# nguyen_l.net
KiCad netlist of a schematic drawn in Altium Designer
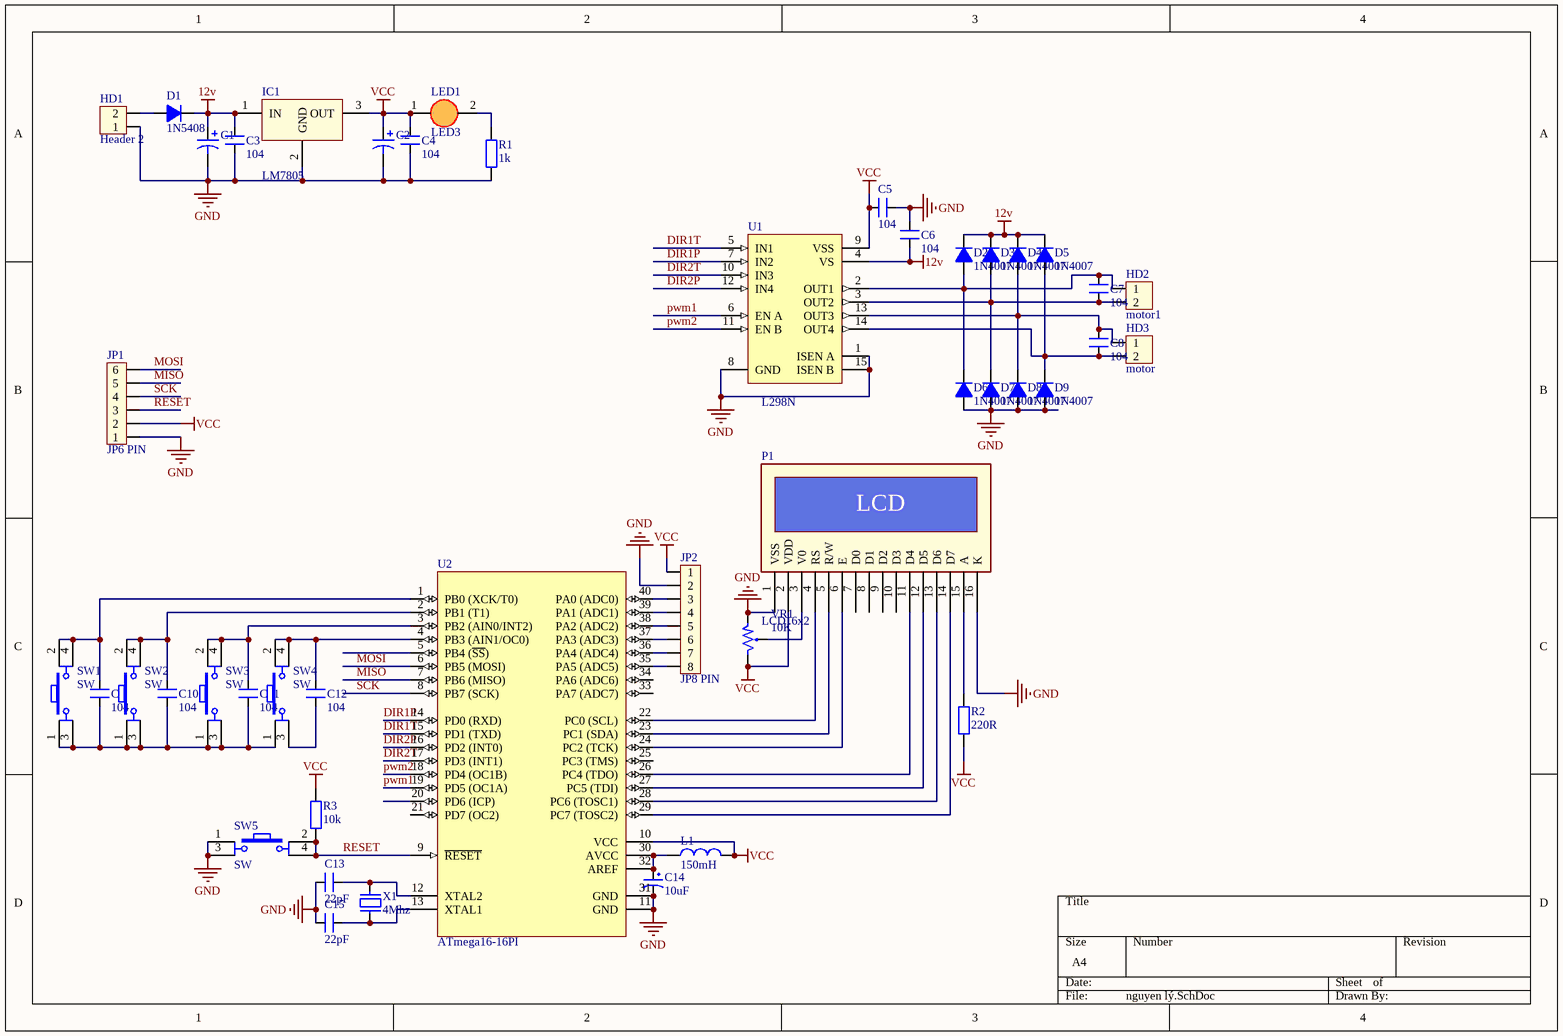
[diagram p0: nguyen lý.SchDoc]

(export (version "E")
  (design (tool "Eeschema 10.0.6"))
  (components
    (comp (ref "C1")
      (value "Cap Pol 8mm")
      (footprint "C10mm")
      (description "Polarized Capacitor (Axial)")
      (fields (field (name "PUBLISHER") "Altium Limited"))
      (libsource (lib "thu vien") (part "Cap Pol 8mm"))
    )
    (comp (ref "C2")
      (value "Cap Pol 8mm")
      (footprint "C10mm")
      (description "Polarized Capacitor (Axial)")
      (fields (field (name "PUBLISHER") "Altium Limited"))
      (libsource (lib "thu vien") (part "Cap Pol 8mm"))
    )
    (comp (ref "C3")
      (value "104")
      (footprint "CN2")
      (description "Cap np Cremic Value  104pF => 105pF")
      (libsource (lib "syhaunguyen") (part "CN2"))
    )
    (comp (ref "C4")
      (value "104")
      (footprint "CN2")
      (description "Cap np Cremic Value  104pF => 105pF")
      (libsource (lib "syhaunguyen") (part "CN2"))
    )
    (comp (ref "C5")
      (value "104")
      (footprint "CN2")
      (description "Cap np Cremic Value  104pF => 105pF")
      (libsource (lib "syhaunguyen") (part "CN2"))
    )
    (comp (ref "C6")
      (value "104")
      (footprint "CN2")
      (description "Cap np Cremic Value  104pF => 105pF")
      (libsource (lib "syhaunguyen") (part "CN2"))
    )
    (comp (ref "C7")
      (value "104")
      (footprint "CN2")
      (description "Cap np Cremic Value  104pF => 105pF")
      (libsource (lib "syhaunguyen") (part "CN2"))
    )
    (comp (ref "C8")
      (value "104")
      (footprint "CN2")
      (description "Cap np Cremic Value  104pF => 105pF")
      (libsource (lib "syhaunguyen") (part "CN2"))
    )
    (comp (ref "C9")
      (value "104")
      (footprint "CN1.5")
      (description "Cap np Cremic  682pF => 104 pF")
      (libsource (lib "syhaunguyen") (part "CN1.5"))
    )
    (comp (ref "C10")
      (value "104")
      (footprint "CN1.5")
      (description "Cap np Cremic  682pF => 104 pF")
      (libsource (lib "syhaunguyen") (part "CN1.5"))
    )
    (comp (ref "C11")
      (value "104")
      (footprint "CN1.5")
      (description "Cap np Cremic  682pF => 104 pF")
      (libsource (lib "syhaunguyen") (part "CN1.5"))
    )
    (comp (ref "C12")
      (value "104")
      (footprint "CN1.5")
      (description "Cap np Cremic  682pF => 104 pF")
      (libsource (lib "syhaunguyen") (part "CN1.5"))
    )
    (comp (ref "C13")
      (value "22pF")
      (footprint "CN1")
      (description "Cap np Cremic Value  1pF => 472 pF")
      (libsource (lib "syhaunguyen") (part "CN1"))
    )
    (comp (ref "C14")
      (value "10uF")
      (footprint "CP1/2")
      (description "Cap P  0,1uF < 22uF , 16 - 50V")
      (libsource (lib "syhaunguyen") (part "CP1"))
    )
    (comp (ref "C15")
      (value "22pF")
      (footprint "CN1")
      (description "Cap np Cremic Value  1pF => 472 pF")
      (libsource (lib "syhaunguyen") (part "CN1"))
    )
    (comp (ref "D1")
      (value "1N5408")
      (footprint "D5A")
      (description "Diode 5A")
      (libsource (lib "syhaunguyen") (part "D5A"))
    )
    (comp (ref "D2")
      (value "1N4007")
      (footprint "D1A")
      (description "Diode 1A")
      (libsource (lib "syhaunguyen") (part "D1A"))
    )
    (comp (ref "D3")
      (value "1N4007")
      (footprint "D1A")
      (description "Diode 1A")
      (libsource (lib "syhaunguyen") (part "D1A"))
    )
    (comp (ref "D4")
      (value "1N4007")
      (footprint "D1A")
      (description "Diode 1A")
      (libsource (lib "syhaunguyen") (part "D1A"))
    )
    (comp (ref "D5")
      (value "1N4007")
      (footprint "D1A")
      (description "Diode 1A")
      (libsource (lib "syhaunguyen") (part "D1A"))
    )
    (comp (ref "D6")
      (value "1N4007")
      (footprint "D1A")
      (description "Diode 1A")
      (libsource (lib "syhaunguyen") (part "D1A"))
    )
    (comp (ref "D7")
      (value "1N4007")
      (footprint "D1A")
      (description "Diode 1A")
      (libsource (lib "syhaunguyen") (part "D1A"))
    )
    (comp (ref "D8")
      (value "1N4007")
      (footprint "D1A")
      (description "Diode 1A")
      (libsource (lib "syhaunguyen") (part "D1A"))
    )
    (comp (ref "D9")
      (value "1N4007")
      (footprint "D1A")
      (description "Diode 1A")
      (libsource (lib "syhaunguyen") (part "D1A"))
    )
    (comp (ref "HD1")
      (value "Header 2")
      (footprint "HED2")
      (description "Header 2 (Green)")
      (libsource (lib "") (part "Hed2_1"))
    )
    (comp (ref "HD2")
      (value "motor1")
      (footprint "HED2")
      (description "Header 2 (Green)")
      (libsource (lib "syhaunguyen") (part "Hed2"))
    )
    (comp (ref "HD3")
      (value "motor")
      (footprint "HED2")
      (description "Header 2 (Green)")
      (libsource (lib "syhaunguyen") (part "Hed2"))
    )
    (comp (ref "IC1")
      (value "LM7805")
      (footprint "TO-220")
      (description "On ap +, from + 5 to + 24VDC")
      (libsource (lib "syhaunguyen") (part "LM78xx"))
    )
    (comp (ref "JP1") (value "JP6 PIN") (footprint "JP6") (libsource (lib "syhaunguyen") (part "JP6")))
    (comp (ref "JP2") (value "JP8 PIN") (footprint "JP8") (libsource (lib "syhaunguyen") (part "JP8")))
    (comp (ref "L1")
      (value "150mH")
      (footprint "L/0.4")
      (description "Inductor")
      (libsource (lib "syhaunguyen") (part "L1"))
    )
    (comp (ref "LED1")
      (value "LED3")
      (footprint "LED3mm")
      (description "LED 3mm")
      (libsource (lib "thu vien") (part "LED 3mm"))
    )
    (comp (ref "P1") (value "LCD16x2") (footprint "LCD16X2N") (libsource (lib "thu vien") (part "LCD Text")))
    (comp (ref "R1")
      (value "1k")
      (footprint "R1/4W")
      (description "Resistor 1/4W")
      (libsource (lib "syhaunguyen") (part "R1/4W"))
    )
    (comp (ref "R2")
      (value "220R")
      (footprint "R1/4W")
      (description "Resistor 1/4W")
      (libsource (lib "syhaunguyen") (part "R1/4W"))
    )
    (comp (ref "R3")
      (value "10k")
      (footprint "R1/4W")
      (description "Resistor 1/4W")
      (libsource (lib "syhaunguyen") (part "R1/4W"))
    )
    (comp (ref "SW1")
      (value "SW")
      (footprint "SW4")
      (description "Switch button 4 pin")
      (libsource (lib "syhaunguyen") (part "SW4"))
    )
    (comp (ref "SW2")
      (value "SW")
      (footprint "SW4")
      (description "Switch button 4 pin")
      (libsource (lib "syhaunguyen") (part "SW4"))
    )
    (comp (ref "SW3")
      (value "SW")
      (footprint "SW4")
      (description "Switch button 4 pin")
      (libsource (lib "syhaunguyen") (part "SW4"))
    )
    (comp (ref "SW4")
      (value "SW")
      (footprint "SW4")
      (description "Switch button 4 pin")
      (libsource (lib "syhaunguyen") (part "SW4"))
    )
    (comp (ref "SW5")
      (value "SW")
      (footprint "SW4")
      (description "Switch button 4 pin")
      (libsource (lib "") (part "SW4_1"))
    )
    (comp (ref "U1")
      (value "L298N")
      (footprint "DIP15SL2")
      (description "Dual Full Bridge Driver")
      (fields (field (name "PUBLISHER") "Altium Limited"))
      (libsource (lib "thu vien") (part "L298N"))
    )
    (comp (ref "U2")
      (value "ATmega16-16PI")
      (footprint "DIP40/W0.6")
      (description "8-Bit AVR Microcontroller with 16K Bytes of In-System Programmable Flash Memory")
      (fields (field (name "PUBLISHER") "Altium Limited"))
      (libsource (lib "thu vien") (part "ATmega16-16PI"))
    )
    (comp (ref "VR1")
      (value "10K")
      (footprint "VR1")
      (description "Var Resistor")
      (libsource (lib "syhaunguyen") (part "VR1"))
    )
    (comp (ref "X1")
      (value "4Mhz")
      (footprint "XT2")
      (description "Crystal For all Crystal 2pin.")
      (libsource (lib "syhaunguyen") (part "XT2"))
    )
  )
  (nets
    (net (code "1") (name "/DIR1P") (class "Default")
      (node (ref "U1") (pin "7") (pinfunction "IN2_7") (pintype "input"))
      (node (ref "U2") (pin "14") (pinfunction "PD0_(RXD)_14") (pintype "bidirectional"))
    )
    (net (code "2") (name "/DIR1T") (class "Default")
      (node (ref "U1") (pin "5") (pinfunction "IN1_5") (pintype "input"))
      (node (ref "U2") (pin "15") (pinfunction "PD1_(TXD)_15") (pintype "bidirectional"))
    )
    (net (code "3") (name "/DIR2P") (class "Default")
      (node (ref "U1") (pin "12") (pinfunction "IN4_12") (pintype "input"))
      (node (ref "U2") (pin "16") (pinfunction "PD2_(INT0)_16") (pintype "bidirectional"))
    )
    (net (code "4") (name "/DIR2T") (class "Default")
      (node (ref "U1") (pin "10") (pinfunction "IN3_10") (pintype "input"))
      (node (ref "U2") (pin "17") (pinfunction "PD3_(INT1)_17") (pintype "bidirectional"))
    )
    (net (code "5") (name "/MISO") (class "Default")
      (node (ref "JP1") (pin "5") (pinfunction "5_5") (pintype "passive"))
      (node (ref "U2") (pin "7") (pinfunction "PB6_(MISO)_7") (pintype "bidirectional"))
    )
    (net (code "6") (name "/MOSI") (class "Default")
      (node (ref "JP1") (pin "6") (pinfunction "6_6") (pintype "passive"))
      (node (ref "U2") (pin "6") (pinfunction "PB5_(MOSI)_6") (pintype "bidirectional"))
    )
    (net (code "7") (name "/RESET") (class "Default")
      (node (ref "JP1") (pin "3") (pinfunction "3_3") (pintype "passive"))
      (node (ref "R3") (pin "1") (pinfunction "1_1") (pintype "passive"))
      (node (ref "SW5") (pin "2") (pintype "passive"))
      (node (ref "SW5") (pin "4") (pintype "passive"))
      (node (ref "U2") (pin "9") (pinfunction "~{RESET}_9") (pintype "input"))
    )
    (net (code "8") (name "/SCK") (class "Default")
      (node (ref "JP1") (pin "4") (pinfunction "4_4") (pintype "passive"))
      (node (ref "U2") (pin "8") (pinfunction "PB7_(SCK)_8") (pintype "bidirectional"))
    )
    (net (code "9") (name "/pwm1") (class "Default")
      (node (ref "U1") (pin "6") (pinfunction "EN_A_6") (pintype "input"))
      (node (ref "U2") (pin "19") (pinfunction "PD5_(OC1A)_19") (pintype "bidirectional"))
    )
    (net (code "10") (name "/pwm2") (class "Default")
      (node (ref "U1") (pin "11") (pinfunction "EN_B_11") (pintype "input"))
      (node (ref "U2") (pin "18") (pinfunction "PD4_(OC1B)_18") (pintype "bidirectional"))
    )
    (net (code "11") (name "12v") (class "Default")
      (node (ref "C1") (pin "1") (pinfunction "1_1") (pintype "passive"))
      (node (ref "C3") (pin "2") (pinfunction "2_2") (pintype "passive"))
      (node (ref "C6") (pin "1") (pinfunction "1_1") (pintype "passive"))
      (node (ref "D1") (pin "2") (pinfunction "K_2") (pintype "passive"))
      (node (ref "D2") (pin "2") (pinfunction "K_2") (pintype "passive"))
      (node (ref "D3") (pin "2") (pinfunction "K_2") (pintype "passive"))
      (node (ref "D4") (pin "2") (pinfunction "K_2") (pintype "passive"))
      (node (ref "D5") (pin "2") (pinfunction "K_2") (pintype "passive"))
      (node (ref "IC1") (pin "1") (pinfunction "IN_1") (pintype "passive"))
      (node (ref "U1") (pin "4") (pinfunction "VS_4") (pintype "power_in"))
    )
    (net (code "12") (name "GND") (class "Default")
      (node (ref "C1") (pin "2") (pinfunction "2_2") (pintype "passive"))
      (node (ref "C13") (pin "1") (pinfunction "1_1") (pintype "passive"))
      (node (ref "C14") (pin "2") (pinfunction "2_2") (pintype "passive"))
      (node (ref "C15") (pin "1") (pinfunction "1_1") (pintype "passive"))
      (node (ref "C2") (pin "2") (pinfunction "2_2") (pintype "passive"))
      (node (ref "C3") (pin "1") (pinfunction "1_1") (pintype "passive"))
      (node (ref "C4") (pin "1") (pinfunction "1_1") (pintype "passive"))
      (node (ref "C5") (pin "2") (pinfunction "2_2") (pintype "passive"))
      (node (ref "C6") (pin "2") (pinfunction "2_2") (pintype "passive"))
      (node (ref "D6") (pin "1") (pinfunction "A_1") (pintype "passive"))
      (node (ref "D7") (pin "1") (pinfunction "A_1") (pintype "passive"))
      (node (ref "D8") (pin "1") (pinfunction "A_1") (pintype "passive"))
      (node (ref "D9") (pin "1") (pinfunction "A_1") (pintype "passive"))
      (node (ref "HD1") (pin "1") (pinfunction "1_1") (pintype "passive"))
      (node (ref "IC1") (pin "2") (pinfunction "GND_2") (pintype "passive"))
      (node (ref "JP1") (pin "1") (pinfunction "1_1") (pintype "passive"))
      (node (ref "JP2") (pin "2") (pinfunction "2_2") (pintype "passive"))
      (node (ref "P1") (pin "1") (pinfunction "VSS_1") (pintype "passive"))
      (node (ref "P1") (pin "16") (pinfunction "K_16") (pintype "passive"))
      (node (ref "R1") (pin "1") (pinfunction "1_1") (pintype "passive"))
      (node (ref "SW5") (pin "1") (pintype "passive"))
      (node (ref "SW5") (pin "3") (pintype "passive"))
      (node (ref "U1") (pin "1") (pinfunction "ISEN_A_1") (pintype "passive"))
      (node (ref "U1") (pin "15") (pinfunction "ISEN_B_15") (pintype "passive"))
      (node (ref "U1") (pin "8") (pinfunction "GND_8") (pintype "power_in"))
      (node (ref "U2") (pin "11") (pinfunction "GND_11") (pintype "power_in"))
      (node (ref "U2") (pin "31") (pinfunction "GND_31") (pintype "power_in"))
      (node (ref "VR1") (pin "1") (pinfunction "1_1") (pintype "passive"))
    )
    (net (code "13") (name "Net-(C10-Pad1)") (class "Default")
      (node (ref "C10") (pin "1") (pinfunction "1_1") (pintype "passive"))
      (node (ref "C11") (pin "1") (pinfunction "1_1") (pintype "passive"))
      (node (ref "C9") (pin "1") (pinfunction "1_1") (pintype "passive"))
      (node (ref "SW1") (pin "1") (pintype "passive"))
      (node (ref "SW1") (pin "3") (pintype "passive"))
      (node (ref "SW2") (pin "1") (pintype "passive"))
      (node (ref "SW2") (pin "3") (pintype "passive"))
      (node (ref "SW3") (pin "1") (pintype "passive"))
      (node (ref "SW3") (pin "3") (pintype "passive"))
      (node (ref "SW4") (pin "1") (pintype "passive"))
    )
    (net (code "14") (name "Net-(C12-Pad1)") (class "Default")
      (node (ref "C12") (pin "1") (pinfunction "1_1") (pintype "passive"))
      (node (ref "SW4") (pin "3") (pintype "passive"))
    )
    (net (code "15") (name "Net-(D1-A)") (class "Default")
      (node (ref "D1") (pin "1") (pinfunction "A_1") (pintype "passive"))
      (node (ref "HD1") (pin "2") (pinfunction "2_2") (pintype "passive"))
    )
    (net (code "16") (name "Net-(D2-A)") (class "Default")
      (node (ref "C7") (pin "2") (pinfunction "2_2") (pintype "passive"))
      (node (ref "D2") (pin "1") (pinfunction "A_1") (pintype "passive"))
      (node (ref "D6") (pin "2") (pinfunction "K_2") (pintype "passive"))
      (node (ref "HD2") (pin "1") (pinfunction "1_1") (pintype "passive"))
      (node (ref "U1") (pin "2") (pinfunction "OUT1_2") (pintype "output"))
    )
    (net (code "17") (name "Net-(D3-A)") (class "Default")
      (node (ref "C7") (pin "1") (pinfunction "1_1") (pintype "passive"))
      (node (ref "D3") (pin "1") (pinfunction "A_1") (pintype "passive"))
      (node (ref "D7") (pin "2") (pinfunction "K_2") (pintype "passive"))
      (node (ref "HD2") (pin "2") (pinfunction "2_2") (pintype "passive"))
      (node (ref "U1") (pin "3") (pinfunction "OUT2_3") (pintype "output"))
    )
    (net (code "18") (name "Net-(D4-A)") (class "Default")
      (node (ref "C8") (pin "2") (pinfunction "2_2") (pintype "passive"))
      (node (ref "D4") (pin "1") (pinfunction "A_1") (pintype "passive"))
      (node (ref "D8") (pin "2") (pinfunction "K_2") (pintype "passive"))
      (node (ref "HD3") (pin "1") (pinfunction "1_1") (pintype "passive"))
      (node (ref "U1") (pin "13") (pinfunction "OUT3_13") (pintype "output"))
    )
    (net (code "19") (name "Net-(D5-A)") (class "Default")
      (node (ref "C8") (pin "1") (pinfunction "1_1") (pintype "passive"))
      (node (ref "D5") (pin "1") (pinfunction "A_1") (pintype "passive"))
      (node (ref "D9") (pin "2") (pinfunction "K_2") (pintype "passive"))
      (node (ref "HD3") (pin "2") (pinfunction "2_2") (pintype "passive"))
      (node (ref "U1") (pin "14") (pinfunction "OUT4_14") (pintype "output"))
    )
    (net (code "20") (name "Net-(LED1-K)") (class "Default")
      (node (ref "LED1") (pin "2") (pinfunction "K_2") (pintype "passive"))
      (node (ref "R1") (pin "2") (pinfunction "2_2") (pintype "passive"))
    )
    (net (code "21") (name "Net-(P1-A)") (class "Default")
      (node (ref "P1") (pin "15") (pinfunction "A_15") (pintype "passive"))
      (node (ref "R2") (pin "2") (pinfunction "2_2") (pintype "passive"))
    )
    (net (code "22") (name "Net-(P1-D4)") (class "Default")
      (node (ref "P1") (pin "11") (pinfunction "D4_11") (pintype "passive"))
      (node (ref "U2") (pin "26") (pinfunction "PC4_(TDO)_26") (pintype "bidirectional"))
    )
    (net (code "23") (name "Net-(P1-D5)") (class "Default")
      (node (ref "P1") (pin "12") (pinfunction "D5_12") (pintype "passive"))
      (node (ref "U2") (pin "27") (pinfunction "PC5_(TDI)_27") (pintype "bidirectional"))
    )
    (net (code "24") (name "Net-(P1-D6)") (class "Default")
      (node (ref "P1") (pin "13") (pinfunction "D6_13") (pintype "passive"))
      (node (ref "U2") (pin "28") (pinfunction "PC6_(TOSC1)_28") (pintype "bidirectional"))
    )
    (net (code "25") (name "Net-(P1-D7)") (class "Default")
      (node (ref "P1") (pin "14") (pinfunction "D7_14") (pintype "passive"))
      (node (ref "U2") (pin "29") (pinfunction "PC7_(TOSC2)_29") (pintype "bidirectional"))
    )
    (net (code "26") (name "Net-(P1-E)") (class "Default")
      (node (ref "P1") (pin "6") (pinfunction "E_6") (pintype "passive"))
      (node (ref "U2") (pin "24") (pinfunction "PC2_(TCK)_24") (pintype "bidirectional"))
    )
    (net (code "27") (name "Net-(P1-RS)") (class "Default")
      (node (ref "P1") (pin "4") (pinfunction "RS_4") (pintype "passive"))
      (node (ref "U2") (pin "22") (pinfunction "PC0_(SCL)_22") (pintype "bidirectional"))
    )
    (net (code "28") (name "Net-(P1-R{slash}W)") (class "Default")
      (node (ref "P1") (pin "5") (pinfunction "R/W_5") (pintype "passive"))
      (node (ref "U2") (pin "23") (pinfunction "PC1_(SDA)_23") (pintype "bidirectional"))
    )
    (net (code "29") (name "Net-(P1-V0)") (class "Default")
      (node (ref "P1") (pin "3") (pinfunction "V0_3") (pintype "passive"))
      (node (ref "VR1") (pin "2") (pinfunction "2_2") (pintype "passive"))
    )
    (net (code "30") (name "Net-(U2-AREF)") (class "Default")
      (node (ref "C14") (pin "1") (pinfunction "1_1") (pintype "passive"))
      (node (ref "L1") (pin "1") (pinfunction "1_1") (pintype "passive"))
      (node (ref "U2") (pin "30") (pinfunction "AVCC_30") (pintype "power_in"))
      (node (ref "U2") (pin "32") (pinfunction "AREF_32") (pintype "passive"))
    )
    (net (code "31") (name "Net-(U2-PA0_(ADC0))") (class "Default")
      (node (ref "JP2") (pin "3") (pinfunction "3_3") (pintype "passive"))
      (node (ref "U2") (pin "40") (pinfunction "PA0_(ADC0)_40") (pintype "bidirectional"))
    )
    (net (code "32") (name "Net-(U2-PA1_(ADC1))") (class "Default")
      (node (ref "JP2") (pin "4") (pinfunction "4_4") (pintype "passive"))
      (node (ref "U2") (pin "39") (pinfunction "PA1_(ADC1)_39") (pintype "bidirectional"))
    )
    (net (code "33") (name "Net-(U2-PA2_(ADC2))") (class "Default")
      (node (ref "JP2") (pin "5") (pinfunction "5_5") (pintype "passive"))
      (node (ref "U2") (pin "38") (pinfunction "PA2_(ADC2)_38") (pintype "bidirectional"))
    )
    (net (code "34") (name "Net-(U2-PA3_(ADC3))") (class "Default")
      (node (ref "JP2") (pin "6") (pinfunction "6_6") (pintype "passive"))
      (node (ref "U2") (pin "37") (pinfunction "PA3_(ADC3)_37") (pintype "bidirectional"))
    )
    (net (code "35") (name "Net-(U2-PA4_(ADC4))") (class "Default")
      (node (ref "JP2") (pin "7") (pinfunction "7_7") (pintype "passive"))
      (node (ref "U2") (pin "36") (pinfunction "PA4_(ADC4)_36") (pintype "bidirectional"))
    )
    (net (code "36") (name "Net-(U2-PA5_(ADC5))") (class "Default")
      (node (ref "JP2") (pin "8") (pinfunction "8_8") (pintype "passive"))
      (node (ref "U2") (pin "35") (pinfunction "PA5_(ADC5)_35") (pintype "bidirectional"))
    )
    (net (code "37") (name "Net-(U2-PB0_(XCK{slash}T0))") (class "Default")
      (node (ref "C9") (pin "2") (pinfunction "2_2") (pintype "passive"))
      (node (ref "SW1") (pin "2") (pintype "passive"))
      (node (ref "SW1") (pin "4") (pintype "passive"))
      (node (ref "U2") (pin "1") (pinfunction "PB0_(XCK/T0)_1") (pintype "bidirectional"))
    )
    (net (code "38") (name "Net-(U2-PB1_(T1))") (class "Default")
      (node (ref "C10") (pin "2") (pinfunction "2_2") (pintype "passive"))
      (node (ref "SW2") (pin "2") (pintype "passive"))
      (node (ref "SW2") (pin "4") (pintype "passive"))
      (node (ref "U2") (pin "2") (pinfunction "PB1_(T1)_2") (pintype "bidirectional"))
    )
    (net (code "39") (name "Net-(U2-PB2_(AIN0{slash}INT2))") (class "Default")
      (node (ref "C11") (pin "2") (pinfunction "2_2") (pintype "passive"))
      (node (ref "SW3") (pin "2") (pintype "passive"))
      (node (ref "SW3") (pin "4") (pintype "passive"))
      (node (ref "U2") (pin "3") (pinfunction "PB2_(AIN0/INT2)_3") (pintype "bidirectional"))
    )
    (net (code "40") (name "Net-(U2-PB3_(AIN1{slash}OC0))") (class "Default")
      (node (ref "C12") (pin "2") (pinfunction "2_2") (pintype "passive"))
      (node (ref "SW4") (pin "2") (pintype "passive"))
      (node (ref "SW4") (pin "4") (pintype "passive"))
      (node (ref "U2") (pin "4") (pinfunction "PB3_(AIN1/OC0)_4") (pintype "bidirectional"))
    )
    (net (code "41") (name "Net-(U2-XTAL1)") (class "Default")
      (node (ref "C15") (pin "2") (pinfunction "2_2") (pintype "passive"))
      (node (ref "U2") (pin "13") (pinfunction "XTAL1_13") (pintype "passive"))
      (node (ref "X1") (pin "1") (pinfunction "1_1") (pintype "passive"))
    )
    (net (code "42") (name "Net-(U2-XTAL2)") (class "Default")
      (node (ref "C13") (pin "2") (pinfunction "2_2") (pintype "passive"))
      (node (ref "U2") (pin "12") (pinfunction "XTAL2_12") (pintype "passive"))
      (node (ref "X1") (pin "2") (pinfunction "2_2") (pintype "passive"))
    )
    (net (code "43") (name "VCC") (class "Default")
      (node (ref "C2") (pin "1") (pinfunction "1_1") (pintype "passive"))
      (node (ref "C4") (pin "2") (pinfunction "2_2") (pintype "passive"))
      (node (ref "C5") (pin "1") (pinfunction "1_1") (pintype "passive"))
      (node (ref "IC1") (pin "3") (pinfunction "OUT_3") (pintype "passive"))
      (node (ref "JP1") (pin "2") (pinfunction "2_2") (pintype "passive"))
      (node (ref "JP2") (pin "1") (pinfunction "1_1") (pintype "passive"))
      (node (ref "L1") (pin "2") (pinfunction "2_2") (pintype "passive"))
      (node (ref "LED1") (pin "1") (pinfunction "A_1") (pintype "passive"))
      (node (ref "P1") (pin "2") (pinfunction "VDD_2") (pintype "passive"))
      (node (ref "R2") (pin "1") (pinfunction "1_1") (pintype "passive"))
      (node (ref "R3") (pin "2") (pinfunction "2_2") (pintype "passive"))
      (node (ref "U1") (pin "9") (pinfunction "VSS_9") (pintype "power_in"))
      (node (ref "U2") (pin "10") (pinfunction "VCC_10") (pintype "power_in"))
      (node (ref "VR1") (pin "3") (pinfunction "3_3") (pintype "passive"))
    )
    (net (code "44") (name "unconnected-(P1-D0-Pad7)") (class "Default")
      (node (ref "P1") (pin "7") (pinfunction "D0_7") (pintype "passive"))
    )
    (net (code "45") (name "unconnected-(P1-D1-Pad8)") (class "Default")
      (node (ref "P1") (pin "8") (pinfunction "D1_8") (pintype "passive"))
    )
    (net (code "46") (name "unconnected-(P1-D2-Pad9)") (class "Default")
      (node (ref "P1") (pin "9") (pinfunction "D2_9") (pintype "passive"))
    )
    (net (code "47") (name "unconnected-(P1-D3-Pad10)") (class "Default")
      (node (ref "P1") (pin "10") (pinfunction "D3_10") (pintype "passive"))
    )
    (net (code "48") (name "unconnected-(U2-PA6_(ADC6)-Pad34)") (class "Default")
      (node (ref "U2") (pin "34") (pinfunction "PA6_(ADC6)_34") (pintype "bidirectional"))
    )
    (net (code "49") (name "unconnected-(U2-PA7_(ADC7)-Pad33)") (class "Default")
      (node (ref "U2") (pin "33") (pinfunction "PA7_(ADC7)_33") (pintype "bidirectional"))
    )
    (net (code "50") (name "unconnected-(U2-PB4_(~{SS})-Pad5)") (class "Default")
      (node (ref "U2") (pin "5") (pinfunction "PB4_(~{SS})_5") (pintype "bidirectional"))
    )
    (net (code "51") (name "unconnected-(U2-PC3_(TMS)-Pad25)") (class "Default")
      (node (ref "U2") (pin "25") (pinfunction "PC3_(TMS)_25") (pintype "bidirectional"))
    )
    (net (code "52") (name "unconnected-(U2-PD6_(ICP)-Pad20)") (class "Default")
      (node (ref "U2") (pin "20") (pinfunction "PD6_(ICP)_20") (pintype "bidirectional"))
    )
    (net (code "53") (name "unconnected-(U2-PD7_(OC2)-Pad21)") (class "Default")
      (node (ref "U2") (pin "21") (pinfunction "PD7_(OC2)_21") (pintype "bidirectional"))
    )
  )
)
